# coil-control-module-v4.net
KiCad netlist of a schematic drawn in EAGLE
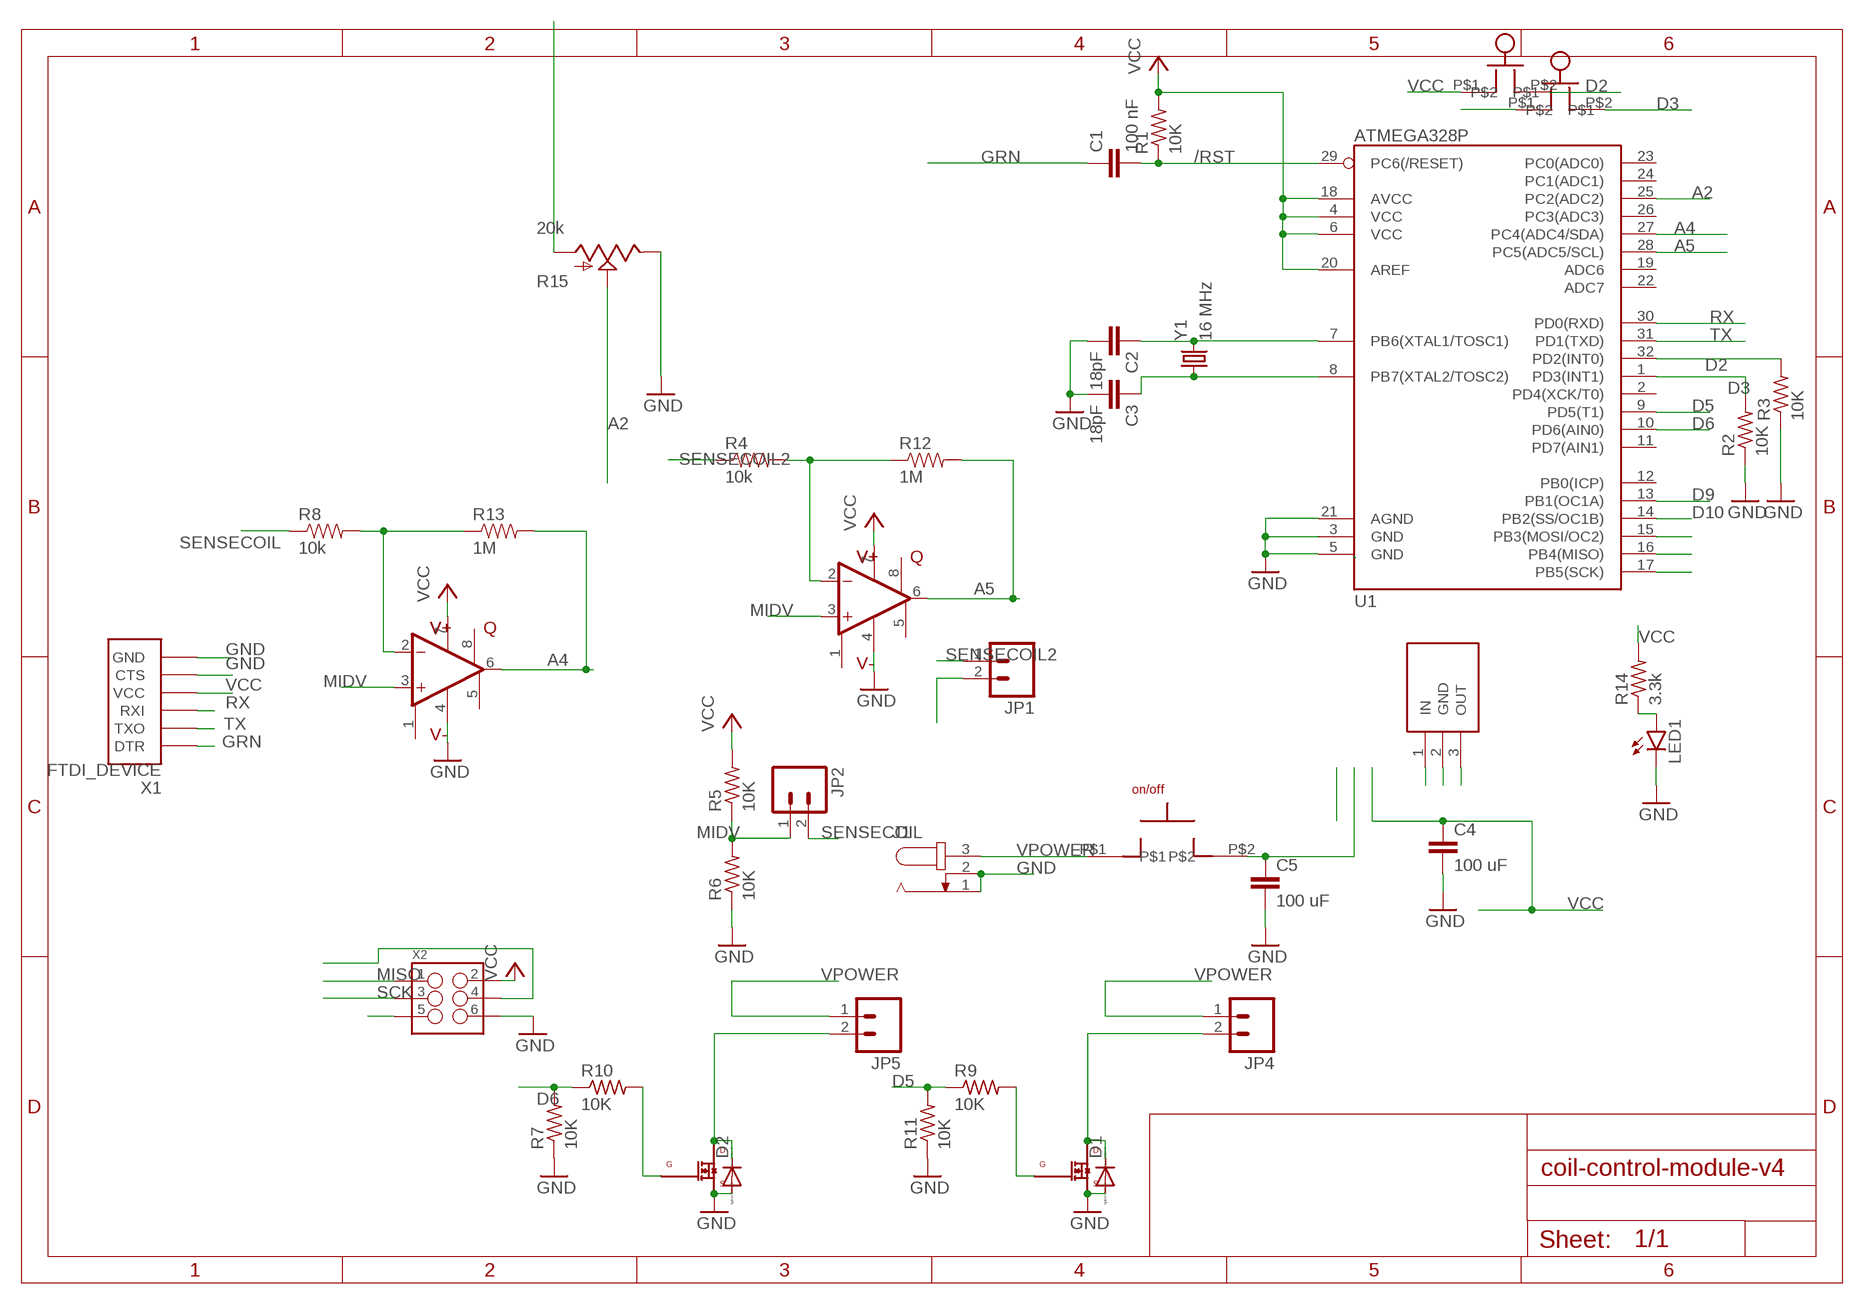
[diagram p0: schematic, sheet 1]

(export (version "E")
  (design (tool "Eeschema 10.0.6"))
  (components
    (comp (ref "C1")
      (value "100 nF")
      (footprint "eagle-import:0603-CAP")
      (libsource (lib "eagle-import") (part "SparkFun-Passives_CAP0603-CAP"))
    )
    (comp (ref "C2")
      (value "18pF")
      (footprint "eagle-import:C0603")
      (libsource (lib "eagle-import") (part "C-EUC0603"))
    )
    (comp (ref "C3")
      (value "18pF")
      (footprint "eagle-import:C0603")
      (libsource (lib "eagle-import") (part "C-EUC0603"))
    )
    (comp (ref "C4")
      (value "100 uF")
      (footprint "eagle-import:1206")
      (libsource (lib "eagle-import") (part "CAP1206"))
    )
    (comp (ref "C5")
      (value "100 uF")
      (footprint "eagle-import:1206")
      (libsource (lib "eagle-import") (part "CAP1206"))
    )
    (comp (ref "D1")
      (value "DIODE-DO-214AC")
      (footprint "eagle-import:DO-214AC")
      (libsource (lib "eagle-import") (part "DIODE-DO-214AC"))
    )
    (comp (ref "D2")
      (value "DIODE-DO-214AC")
      (footprint "eagle-import:DO-214AC")
      (libsource (lib "eagle-import") (part "DIODE-DO-214AC"))
    )
    (comp (ref "J1")
      (value "JACK-PLUG1")
      (footprint "eagle-import:SPC4078")
      (libsource (lib "eagle-import") (part "JACK-PLUG1"))
    )
    (comp (ref "JP1")
      (value "M02PTH")
      (footprint "eagle-import:1X02")
      (libsource (lib "eagle-import") (part "M02PTH"))
    )
    (comp (ref "JP2")
      (value "M02PTH")
      (footprint "eagle-import:1X02")
      (libsource (lib "eagle-import") (part "M02PTH"))
    )
    (comp (ref "JP4")
      (value "M02PTH")
      (footprint "eagle-import:1X02")
      (libsource (lib "eagle-import") (part "M02PTH"))
    )
    (comp (ref "JP5")
      (value "M02PTH")
      (footprint "eagle-import:1X02")
      (libsource (lib "eagle-import") (part "M02PTH"))
    )
    (comp (ref "LED1")
      (value "LED-3MM-NO_SILK")
      (footprint "eagle-import:LED3MM-NS")
      (libsource (lib "eagle-import") (part "LED-3MM-NO_SILK"))
    )
    (comp (ref "Q1")
      (value "IRLML0060")
      (footprint "eagle-import:SOT-23")
      (libsource (lib "eagle-import") (part "IRLML0060"))
    )
    (comp (ref "Q2")
      (value "IRLML0060")
      (footprint "eagle-import:SOT-23")
      (libsource (lib "eagle-import") (part "IRLML0060"))
    )
    (comp (ref "R1")
      (value "10K")
      (footprint "eagle-import:R0603")
      (libsource (lib "eagle-import") (part "R-US_R0603"))
    )
    (comp (ref "R2")
      (value "10K")
      (footprint "eagle-import:R0603")
      (libsource (lib "eagle-import") (part "R-US_R0603"))
    )
    (comp (ref "R3")
      (value "10K")
      (footprint "eagle-import:R0603")
      (libsource (lib "eagle-import") (part "R-US_R0603"))
    )
    (comp (ref "R4")
      (value "10k")
      (footprint "eagle-import:0603-RES")
      (libsource (lib "eagle-import") (part "RESISTOR0603"))
    )
    (comp (ref "R5")
      (value "10K")
      (footprint "eagle-import:R0603")
      (libsource (lib "eagle-import") (part "R-US_R0603"))
    )
    (comp (ref "R6")
      (value "10K")
      (footprint "eagle-import:R0603")
      (libsource (lib "eagle-import") (part "R-US_R0603"))
    )
    (comp (ref "R7")
      (value "10K")
      (footprint "eagle-import:R0603")
      (libsource (lib "eagle-import") (part "R-US_R0603"))
    )
    (comp (ref "R8")
      (value "10k")
      (footprint "eagle-import:0603-RES")
      (libsource (lib "eagle-import") (part "RESISTOR0603"))
    )
    (comp (ref "R9")
      (value "10K")
      (footprint "eagle-import:R0603")
      (libsource (lib "eagle-import") (part "R-US_R0603"))
    )
    (comp (ref "R10")
      (value "10K")
      (footprint "eagle-import:R0603")
      (libsource (lib "eagle-import") (part "R-US_R0603"))
    )
    (comp (ref "R11")
      (value "10K")
      (footprint "eagle-import:R0603")
      (libsource (lib "eagle-import") (part "R-US_R0603"))
    )
    (comp (ref "R12")
      (value "1M")
      (footprint "eagle-import:0805")
      (libsource (lib "eagle-import") (part "RESISTOR0805-RES"))
    )
    (comp (ref "R13")
      (value "1M")
      (footprint "eagle-import:0805")
      (libsource (lib "eagle-import") (part "RESISTOR0805-RES"))
    )
    (comp (ref "R14")
      (value "3.3k")
      (footprint "eagle-import:R0603")
      (libsource (lib "eagle-import") (part "R-US_R0603"))
    )
    (comp (ref "R15")
      (value "20k")
      (footprint "eagle-import:ALPS_POT_KIT")
      (libsource (lib "eagle-import") (part "POTALPS-KIT"))
    )
    (comp (ref "SW1")
      (value "CW182-ND")
      (footprint "eagle-import:CW182-ND")
      (libsource (lib "eagle-import") (part "CW182-ND"))
    )
    (comp (ref "SW2")
      (value "BUTTON")
      (footprint "eagle-import:BUTTON")
      (libsource (lib "eagle-import") (part "BUTTON"))
    )
    (comp (ref "SW3")
      (value "BUTTON")
      (footprint "eagle-import:BUTTON")
      (libsource (lib "eagle-import") (part "BUTTON"))
    )
    (comp (ref "U1")
      (value "ATMEGA328P")
      (footprint "eagle-import:TQFP32-08")
      (libsource (lib "eagle-import") (part "ATMEGA328_SMT"))
    )
    (comp (ref "U2")
      (value "LM4250")
      (footprint "eagle-import:DIP08")
      (libsource (lib "eagle-import") (part "LM4250"))
    )
    (comp (ref "U3")
      (value "LM4250")
      (footprint "eagle-import:DIP08")
      (libsource (lib "eagle-import") (part "LM4250"))
    )
    (comp (ref "U5")
      (value "L78L33ABZ-AP")
      (footprint "eagle-import:TO92-3")
      (libsource (lib "eagle-import") (part "L78L33ABZ-AP"))
    )
    (comp (ref "X1")
      (value "FTDI_DEVICE")
      (footprint "eagle-import:FTDI_DEVICE_SIDE")
      (libsource (lib "eagle-import") (part "FTDI_DEVICE"))
    )
    (comp (ref "X2")
      (value "M03X2NO_SILK")
      (footprint "eagle-import:2X3-NS")
      (libsource (lib "eagle-import") (part "M03X2NO_SILK"))
    )
    (comp (ref "Y1")
      (value "16 MHz")
      (footprint "eagle-import:CRYSTAL-SMD-5X3")
      (libsource (lib "eagle-import") (part "CRYSTAL5X3"))
    )
  )
  (nets
    (net (code "1") (name "/A2") (class "Default")
      (node (ref "R15") (pin "P$2") (pinfunction "S_P$2") (pintype "passive"))
      (node (ref "U1") (pin "25") (pinfunction "PC2(ADC2)_25") (pintype "bidirectional"))
    )
    (net (code "2") (name "/A4") (class "Default")
      (node (ref "R13") (pin "2") (pinfunction "2_2") (pintype "passive"))
      (node (ref "U1") (pin "27") (pinfunction "PC4(ADC4/SDA)_27") (pintype "bidirectional"))
      (node (ref "U2") (pin "6") (pinfunction "OUT_6") (pintype "output"))
    )
    (net (code "3") (name "/A5") (class "Default")
      (node (ref "R12") (pin "2") (pinfunction "2_2") (pintype "passive"))
      (node (ref "U1") (pin "28") (pinfunction "PC5(ADC5/SCL)_28") (pintype "bidirectional"))
      (node (ref "U3") (pin "6") (pinfunction "OUT_6") (pintype "output"))
    )
    (net (code "4") (name "/D2") (class "Default")
      (node (ref "R3") (pin "2") (pinfunction "2_2") (pintype "passive"))
      (node (ref "SW2") (pin "P$2") (pinfunction "P$2_P$2") (pintype "bidirectional"))
      (node (ref "U1") (pin "32") (pinfunction "PD2(INT0)_32") (pintype "bidirectional"))
    )
    (net (code "5") (name "/D3") (class "Default")
      (node (ref "R2") (pin "2") (pinfunction "2_2") (pintype "passive"))
      (node (ref "SW3") (pin "P$2") (pinfunction "P$2_P$2") (pintype "bidirectional"))
      (node (ref "U1") (pin "1") (pinfunction "PD3(INT1)_1") (pintype "bidirectional"))
    )
    (net (code "6") (name "/D5") (class "Default")
      (node (ref "R11") (pin "2") (pinfunction "2_2") (pintype "passive"))
      (node (ref "R9") (pin "1") (pinfunction "1_1") (pintype "passive"))
      (node (ref "U1") (pin "9") (pinfunction "PD5(T1)_9") (pintype "bidirectional"))
    )
    (net (code "7") (name "/D6") (class "Default")
      (node (ref "R10") (pin "1") (pinfunction "1_1") (pintype "passive"))
      (node (ref "R7") (pin "2") (pinfunction "2_2") (pintype "passive"))
      (node (ref "U1") (pin "10") (pinfunction "PD6(AIN0)_10") (pintype "bidirectional"))
    )
    (net (code "8") (name "/D9") (class "Default")
      (node (ref "U1") (pin "13") (pinfunction "PB1(OC1A)_13") (pintype "bidirectional"))
    )
    (net (code "9") (name "/D10") (class "Default")
      (node (ref "U1") (pin "14") (pinfunction "PB2(SS/OC1B)_14") (pintype "bidirectional"))
    )
    (net (code "10") (name "/GRN") (class "Default")
      (node (ref "C1") (pin "1") (pinfunction "1_1") (pintype "passive"))
      (node (ref "X1") (pin "P$1") (pinfunction "DTR_P$1") (pintype "bidirectional"))
    )
    (net (code "11") (name "/MIDV") (class "Default")
      (node (ref "JP1") (pin "2") (pinfunction "2_2") (pintype "passive"))
      (node (ref "JP2") (pin "1") (pinfunction "1_1") (pintype "passive"))
      (node (ref "R5") (pin "1") (pinfunction "1_1") (pintype "passive"))
      (node (ref "R6") (pin "2") (pinfunction "2_2") (pintype "passive"))
      (node (ref "U2") (pin "3") (pinfunction "+IN_3") (pintype "input"))
      (node (ref "U3") (pin "3") (pinfunction "+IN_3") (pintype "input"))
    )
    (net (code "12") (name "/MISO") (class "Default")
      (node (ref "U1") (pin "16") (pinfunction "PB4(MISO)_16") (pintype "bidirectional"))
      (node (ref "X2") (pin "1") (pinfunction "1_1") (pintype "bidirectional"))
    )
    (net (code "13") (name "/MOSI") (class "Default")
      (node (ref "U1") (pin "15") (pinfunction "PB3(MOSI/OC2)_15") (pintype "bidirectional"))
      (node (ref "X2") (pin "4") (pinfunction "4_4") (pintype "bidirectional"))
    )
    (net (code "14") (name "/RX") (class "Default")
      (node (ref "U1") (pin "30") (pinfunction "PD0(RXD)_30") (pintype "bidirectional"))
      (node (ref "X1") (pin "P$3") (pinfunction "RXI_P$3") (pintype "bidirectional"))
    )
    (net (code "15") (name "/SCK") (class "Default")
      (node (ref "U1") (pin "17") (pinfunction "PB5(SCK)_17") (pintype "bidirectional"))
      (node (ref "X2") (pin "3") (pinfunction "3_3") (pintype "bidirectional"))
    )
    (net (code "16") (name "/SENSECOIL") (class "Default")
      (node (ref "JP2") (pin "2") (pinfunction "2_2") (pintype "passive"))
      (node (ref "R8") (pin "1") (pinfunction "1_1") (pintype "passive"))
    )
    (net (code "17") (name "/SENSECOIL2") (class "Default")
      (node (ref "JP1") (pin "1") (pinfunction "1_1") (pintype "passive"))
      (node (ref "R4") (pin "1") (pinfunction "1_1") (pintype "passive"))
    )
    (net (code "18") (name "/TX") (class "Default")
      (node (ref "U1") (pin "31") (pinfunction "PD1(TXD)_31") (pintype "bidirectional"))
      (node (ref "X1") (pin "P$2") (pinfunction "TXO_P$2") (pintype "bidirectional"))
    )
    (net (code "19") (name "/VIN") (class "Default")
      (node (ref "C5") (pin "1") (pinfunction "1_1") (pintype "passive"))
      (node (ref "SW1") (pin "P$2") (pinfunction "P$2_P$2") (pintype "bidirectional"))
      (node (ref "U5") (pin "1") (pinfunction "IN_1") (pintype "bidirectional"))
    )
    (net (code "20") (name "/VPOWER") (class "Default")
      (node (ref "J1") (pin "3") (pinfunction "3_3") (pintype "passive"))
      (node (ref "JP4") (pin "1") (pinfunction "1_1") (pintype "passive"))
      (node (ref "JP5") (pin "1") (pinfunction "1_1") (pintype "passive"))
      (node (ref "SW1") (pin "P$1") (pinfunction "P$1_P$1") (pintype "bidirectional"))
    )
    (net (code "21") (name "/{slash}RST") (class "Default")
      (node (ref "C1") (pin "2") (pinfunction "2_2") (pintype "passive"))
      (node (ref "R1") (pin "1") (pinfunction "1_1") (pintype "passive"))
      (node (ref "U1") (pin "29") (pinfunction "PC6(/RESET)_29") (pintype "bidirectional"))
      (node (ref "X2") (pin "5") (pinfunction "5_5") (pintype "bidirectional"))
    )
    (net (code "22") (name "GND") (class "Default")
      (node (ref "C2") (pin "2") (pinfunction "2_2") (pintype "passive"))
      (node (ref "C3") (pin "2") (pinfunction "2_2") (pintype "passive"))
      (node (ref "C4") (pin "2") (pinfunction "2_2") (pintype "passive"))
      (node (ref "C5") (pin "2") (pinfunction "2_2") (pintype "passive"))
      (node (ref "D1") (pin "A") (pinfunction "A_A") (pintype "passive"))
      (node (ref "D2") (pin "A") (pinfunction "A_A") (pintype "passive"))
      (node (ref "J1") (pin "1") (pinfunction "1_1") (pintype "passive"))
      (node (ref "J1") (pin "2") (pinfunction "2_2") (pintype "passive"))
      (node (ref "LED1") (pin "K") (pinfunction "C_K") (pintype "passive"))
      (node (ref "Q1") (pin "2") (pinfunction "SOURCE_2") (pintype "bidirectional"))
      (node (ref "Q2") (pin "2") (pinfunction "SOURCE_2") (pintype "bidirectional"))
      (node (ref "R11") (pin "1") (pinfunction "1_1") (pintype "passive"))
      (node (ref "R15") (pin "P$1") (pinfunction "E_P$1") (pintype "passive"))
      (node (ref "R2") (pin "1") (pinfunction "1_1") (pintype "passive"))
      (node (ref "R3") (pin "1") (pinfunction "1_1") (pintype "passive"))
      (node (ref "R6") (pin "1") (pinfunction "1_1") (pintype "passive"))
      (node (ref "R7") (pin "1") (pinfunction "1_1") (pintype "passive"))
      (node (ref "U1") (pin "21") (pinfunction "AGND_21") (pintype "bidirectional"))
      (node (ref "U1") (pin "3") (pinfunction "GND_3") (pintype "bidirectional"))
      (node (ref "U1") (pin "5") (pinfunction "GND_5") (pintype "bidirectional"))
      (node (ref "U2") (pin "4") (pinfunction "V-_4") (pintype "power_in"))
      (node (ref "U3") (pin "4") (pinfunction "V-_4") (pintype "power_in"))
      (node (ref "U5") (pin "2") (pinfunction "GND_2") (pintype "bidirectional"))
      (node (ref "X1") (pin "P$5") (pinfunction "CTS_P$5") (pintype "bidirectional"))
      (node (ref "X1") (pin "P$6") (pinfunction "GND_P$6") (pintype "bidirectional"))
      (node (ref "X2") (pin "6") (pinfunction "6_6") (pintype "bidirectional"))
    )
    (net (code "23") (name "Net-(LED1-PadA)") (class "Default")
      (node (ref "LED1") (pin "A") (pinfunction "A_A") (pintype "passive"))
      (node (ref "R14") (pin "1") (pinfunction "1_1") (pintype "passive"))
    )
    (net (code "24") (name "Net-(Q1-DRAIN)") (class "Default")
      (node (ref "D1") (pin "C") (pinfunction "C_C") (pintype "passive"))
      (node (ref "JP4") (pin "2") (pinfunction "2_2") (pintype "passive"))
      (node (ref "Q1") (pin "3") (pinfunction "DRAIN_3") (pintype "bidirectional"))
    )
    (net (code "25") (name "Net-(Q1-GATE)") (class "Default")
      (node (ref "Q1") (pin "1") (pinfunction "GATE_1") (pintype "bidirectional"))
      (node (ref "R9") (pin "2") (pinfunction "2_2") (pintype "passive"))
    )
    (net (code "26") (name "Net-(Q2-DRAIN)") (class "Default")
      (node (ref "D2") (pin "C") (pinfunction "C_C") (pintype "passive"))
      (node (ref "JP5") (pin "2") (pinfunction "2_2") (pintype "passive"))
      (node (ref "Q2") (pin "3") (pinfunction "DRAIN_3") (pintype "bidirectional"))
    )
    (net (code "27") (name "Net-(Q2-GATE)") (class "Default")
      (node (ref "Q2") (pin "1") (pinfunction "GATE_1") (pintype "bidirectional"))
      (node (ref "R10") (pin "2") (pinfunction "2_2") (pintype "passive"))
    )
    (net (code "28") (name "Net-(U1-PB6(XTAL1{slash}TOSC1))") (class "Default")
      (node (ref "C2") (pin "1") (pinfunction "1_1") (pintype "passive"))
      (node (ref "U1") (pin "7") (pinfunction "PB6(XTAL1/TOSC1)_7") (pintype "bidirectional"))
      (node (ref "Y1") (pin "3") (pinfunction "2_3") (pintype "passive"))
    )
    (net (code "29") (name "Net-(U1-PB7(XTAL2{slash}TOSC2))") (class "Default")
      (node (ref "C3") (pin "1") (pinfunction "1_1") (pintype "passive"))
      (node (ref "U1") (pin "8") (pinfunction "PB7(XTAL2/TOSC2)_8") (pintype "bidirectional"))
      (node (ref "Y1") (pin "1") (pinfunction "1_1") (pintype "passive"))
    )
    (net (code "30") (name "Net-(U2--IN)") (class "Default")
      (node (ref "R13") (pin "1") (pinfunction "1_1") (pintype "passive"))
      (node (ref "R8") (pin "2") (pinfunction "2_2") (pintype "passive"))
      (node (ref "U2") (pin "2") (pinfunction "-IN_2") (pintype "input"))
    )
    (net (code "31") (name "Net-(U3--IN)") (class "Default")
      (node (ref "R12") (pin "1") (pinfunction "1_1") (pintype "passive"))
      (node (ref "R4") (pin "2") (pinfunction "2_2") (pintype "passive"))
      (node (ref "U3") (pin "2") (pinfunction "-IN_2") (pintype "input"))
    )
    (net (code "32") (name "VCC") (class "Default")
      (node (ref "C4") (pin "1") (pinfunction "1_1") (pintype "passive"))
      (node (ref "R1") (pin "2") (pinfunction "2_2") (pintype "passive"))
      (node (ref "R14") (pin "2") (pinfunction "2_2") (pintype "passive"))
      (node (ref "R15") (pin "P$3") (pinfunction "A_P$3") (pintype "passive"))
      (node (ref "R5") (pin "2") (pinfunction "2_2") (pintype "passive"))
      (node (ref "SW2") (pin "P$1") (pinfunction "P$1_P$1") (pintype "bidirectional"))
      (node (ref "SW3") (pin "P$1") (pinfunction "P$1_P$1") (pintype "bidirectional"))
      (node (ref "U1") (pin "18") (pinfunction "AVCC_18") (pintype "bidirectional"))
      (node (ref "U1") (pin "20") (pinfunction "AREF_20") (pintype "bidirectional"))
      (node (ref "U1") (pin "4") (pinfunction "VCC_4") (pintype "bidirectional"))
      (node (ref "U1") (pin "6") (pinfunction "VCC_6") (pintype "bidirectional"))
      (node (ref "U2") (pin "7") (pinfunction "V+_7") (pintype "power_in"))
      (node (ref "U3") (pin "7") (pinfunction "V+_7") (pintype "power_in"))
      (node (ref "U5") (pin "3") (pinfunction "OUT_3") (pintype "bidirectional"))
      (node (ref "X1") (pin "P$4") (pinfunction "VCC_P$4") (pintype "bidirectional"))
      (node (ref "X2") (pin "2") (pinfunction "2_2") (pintype "bidirectional"))
    )
    (net (code "33") (name "unconnected-(U1-ADC6-Pad19)") (class "Default")
      (node (ref "U1") (pin "19") (pinfunction "ADC6_19") (pintype "bidirectional"))
    )
    (net (code "34") (name "unconnected-(U1-ADC7-Pad22)") (class "Default")
      (node (ref "U1") (pin "22") (pinfunction "ADC7_22") (pintype "bidirectional"))
    )
    (net (code "35") (name "unconnected-(U1-PB0(ICP)-Pad12)") (class "Default")
      (node (ref "U1") (pin "12") (pinfunction "PB0(ICP)_12") (pintype "bidirectional"))
    )
    (net (code "36") (name "unconnected-(U1-PC0(ADC0)-Pad23)") (class "Default")
      (node (ref "U1") (pin "23") (pinfunction "PC0(ADC0)_23") (pintype "bidirectional"))
    )
    (net (code "37") (name "unconnected-(U1-PC1(ADC1)-Pad24)") (class "Default")
      (node (ref "U1") (pin "24") (pinfunction "PC1(ADC1)_24") (pintype "bidirectional"))
    )
    (net (code "38") (name "unconnected-(U1-PC3(ADC3)-Pad26)") (class "Default")
      (node (ref "U1") (pin "26") (pinfunction "PC3(ADC3)_26") (pintype "bidirectional"))
    )
    (net (code "39") (name "unconnected-(U1-PD4(XCK{slash}T0)-Pad2)") (class "Default")
      (node (ref "U1") (pin "2") (pinfunction "PD4(XCK/T0)_2") (pintype "bidirectional"))
    )
    (net (code "40") (name "unconnected-(U1-PD7(AIN1)-Pad11)") (class "Default")
      (node (ref "U1") (pin "11") (pinfunction "PD7(AIN1)_11") (pintype "bidirectional"))
    )
    (net (code "41") (name "unconnected-(U2-NULL1-Pad1)") (class "Default")
      (node (ref "U2") (pin "1") (pinfunction "NULL1_1") (pintype "bidirectional"))
    )
    (net (code "42") (name "unconnected-(U2-NULL2-Pad5)") (class "Default")
      (node (ref "U2") (pin "5") (pinfunction "NULL2_5") (pintype "bidirectional"))
    )
    (net (code "43") (name "unconnected-(U2-QUIES-Pad8)") (class "Default")
      (node (ref "U2") (pin "8") (pinfunction "QUIES_8") (pintype "bidirectional"))
    )
    (net (code "44") (name "unconnected-(U3-NULL1-Pad1)") (class "Default")
      (node (ref "U3") (pin "1") (pinfunction "NULL1_1") (pintype "bidirectional"))
    )
    (net (code "45") (name "unconnected-(U3-NULL2-Pad5)") (class "Default")
      (node (ref "U3") (pin "5") (pinfunction "NULL2_5") (pintype "bidirectional"))
    )
    (net (code "46") (name "unconnected-(U3-QUIES-Pad8)") (class "Default")
      (node (ref "U3") (pin "8") (pinfunction "QUIES_8") (pintype "bidirectional"))
    )
  )
)
